# SpareSwitch.net
KiCad netlist of a schematic drawn in Altium Designer
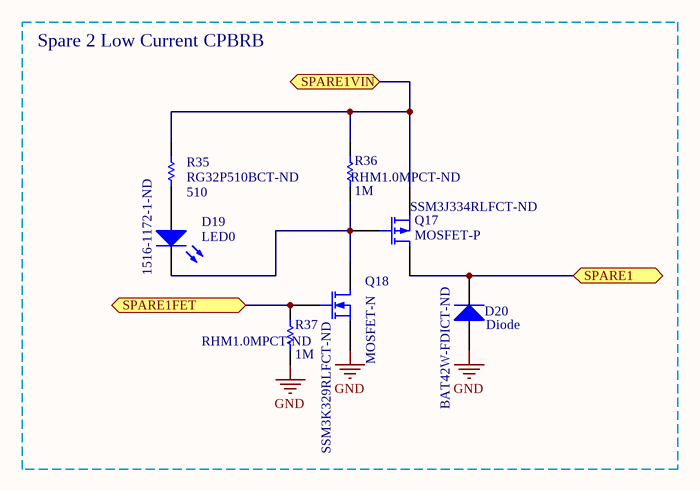
[diagram p0: SpareSwitch.SchDoc]

(export (version "E")
  (design (tool "Eeschema 10.0.6"))
  (components
    (comp (ref "D19")
      (value "LED0")
      (footprint "C1206")
      (description "Typical INFRARED GaAs LED")
      (fields
        (field (name "SUPPLIER PART NUMBER 1") "1516-1172-1-ND")
        (field (name "PUBLISHER") "Altium Limited")
      )
      (libsource (lib "Miscellaneous Devices") (part "LED0"))
    )
    (comp (ref "D20")
      (value "Diode")
      (footprint "sod-123")
      (description "Default Diode")
      (fields
        (field (name "SUPPLIER PART NUMBER 1") "BAT42W-FDICT-ND")
        (field (name "PUBLISHER") "Altium Limited")
      )
      (libsource (lib "Miscellaneous Devices") (part "Diode"))
    )
    (comp (ref "Q17")
      (value "MOSFET-P")
      (footprint "SOT23f")
      (description "P-Channel MOSFET")
      (fields
        (field (name "SUPPLIER PART NUMBER 1") "SSM3J334RLFCT-ND")
        (field (name "PUBLISHER") "Altium Limited")
      )
      (libsource (lib "Miscellaneous Devices") (part "MOSFET-P"))
    )
    (comp (ref "Q18")
      (value "MOSFET-N")
      (footprint "SOT23f")
      (description "N-Channel MOSFET")
      (fields
        (field (name "SUPPLIER PART NUMBER 1") "SSM3K329RLFCT-ND")
        (field (name "PUBLISHER") "Altium Limited")
      )
      (libsource (lib "Miscellaneous Devices") (part "MOSFET-N"))
    )
    (comp (ref "R35")
      (value "510")
      (footprint "C1206")
      (description "Resistor")
      (fields
        (field (name "SUPPLIER PART NUMBER 1") "RG32P510BCT-ND")
        (field (name "Comment") "1206")
        (field (name "PUBLISHER") "Altium Limited")
      )
      (libsource (lib "Miscellaneous Devices") (part "Res1"))
    )
    (comp (ref "R36")
      (value "1M")
      (footprint "C1206")
      (description "Resistor")
      (fields
        (field (name "SUPPLIER PART NUMBER 1") "RHM1.0MPCT-ND")
        (field (name "Comment") "1206")
        (field (name "PUBLISHER") "Altium Limited")
      )
      (libsource (lib "Miscellaneous Devices") (part "Res1"))
    )
    (comp (ref "R37")
      (value "1M")
      (footprint "C1206")
      (description "Resistor")
      (fields
        (field (name "SUPPLIER PART NUMBER 1") "RHM1.0MPCT-ND")
        (field (name "Comment") "1206")
        (field (name "PUBLISHER") "Altium Limited")
      )
      (libsource (lib "Miscellaneous Devices") (part "Res1"))
    )
  )
  (nets
    (net (code "1") (name "/SPARE1") (class "Default")
      (node (ref "D20") (pin "2") (pinfunction "K_2") (pintype "passive"))
      (node (ref "Q17") (pin "1") (pinfunction "D_1") (pintype "passive"))
    )
    (net (code "2") (name "/SPARE1FET") (class "Default")
      (node (ref "Q18") (pin "2") (pinfunction "G_2") (pintype "passive"))
      (node (ref "R37") (pin "2") (pinfunction "2_2") (pintype "passive"))
    )
    (net (code "3") (name "/SPARE1VIN") (class "Default")
      (node (ref "Q17") (pin "3") (pinfunction "S_3") (pintype "passive"))
      (node (ref "R35") (pin "1") (pinfunction "1_1") (pintype "passive"))
      (node (ref "R36") (pin "2") (pinfunction "2_2") (pintype "passive"))
    )
    (net (code "4") (name "GND") (class "Default")
      (node (ref "D20") (pin "1") (pinfunction "A_1") (pintype "passive"))
      (node (ref "Q18") (pin "3") (pinfunction "S_3") (pintype "passive"))
      (node (ref "R37") (pin "1") (pinfunction "1_1") (pintype "passive"))
    )
    (net (code "5") (name "Net-(D19-A)") (class "Default")
      (node (ref "D19") (pin "1") (pinfunction "A_1") (pintype "passive"))
      (node (ref "R35") (pin "2") (pinfunction "2_2") (pintype "passive"))
    )
    (net (code "6") (name "Net-(D19-K)") (class "Default")
      (node (ref "D19") (pin "2") (pinfunction "K_2") (pintype "passive"))
      (node (ref "Q17") (pin "2") (pinfunction "G_2") (pintype "passive"))
      (node (ref "Q18") (pin "1") (pinfunction "D_1") (pintype "passive"))
      (node (ref "R36") (pin "1") (pinfunction "1_1") (pintype "passive"))
    )
  )
)
